# ZHSD-POWER.net
KiCad netlist of a schematic drawn in Altium Designer
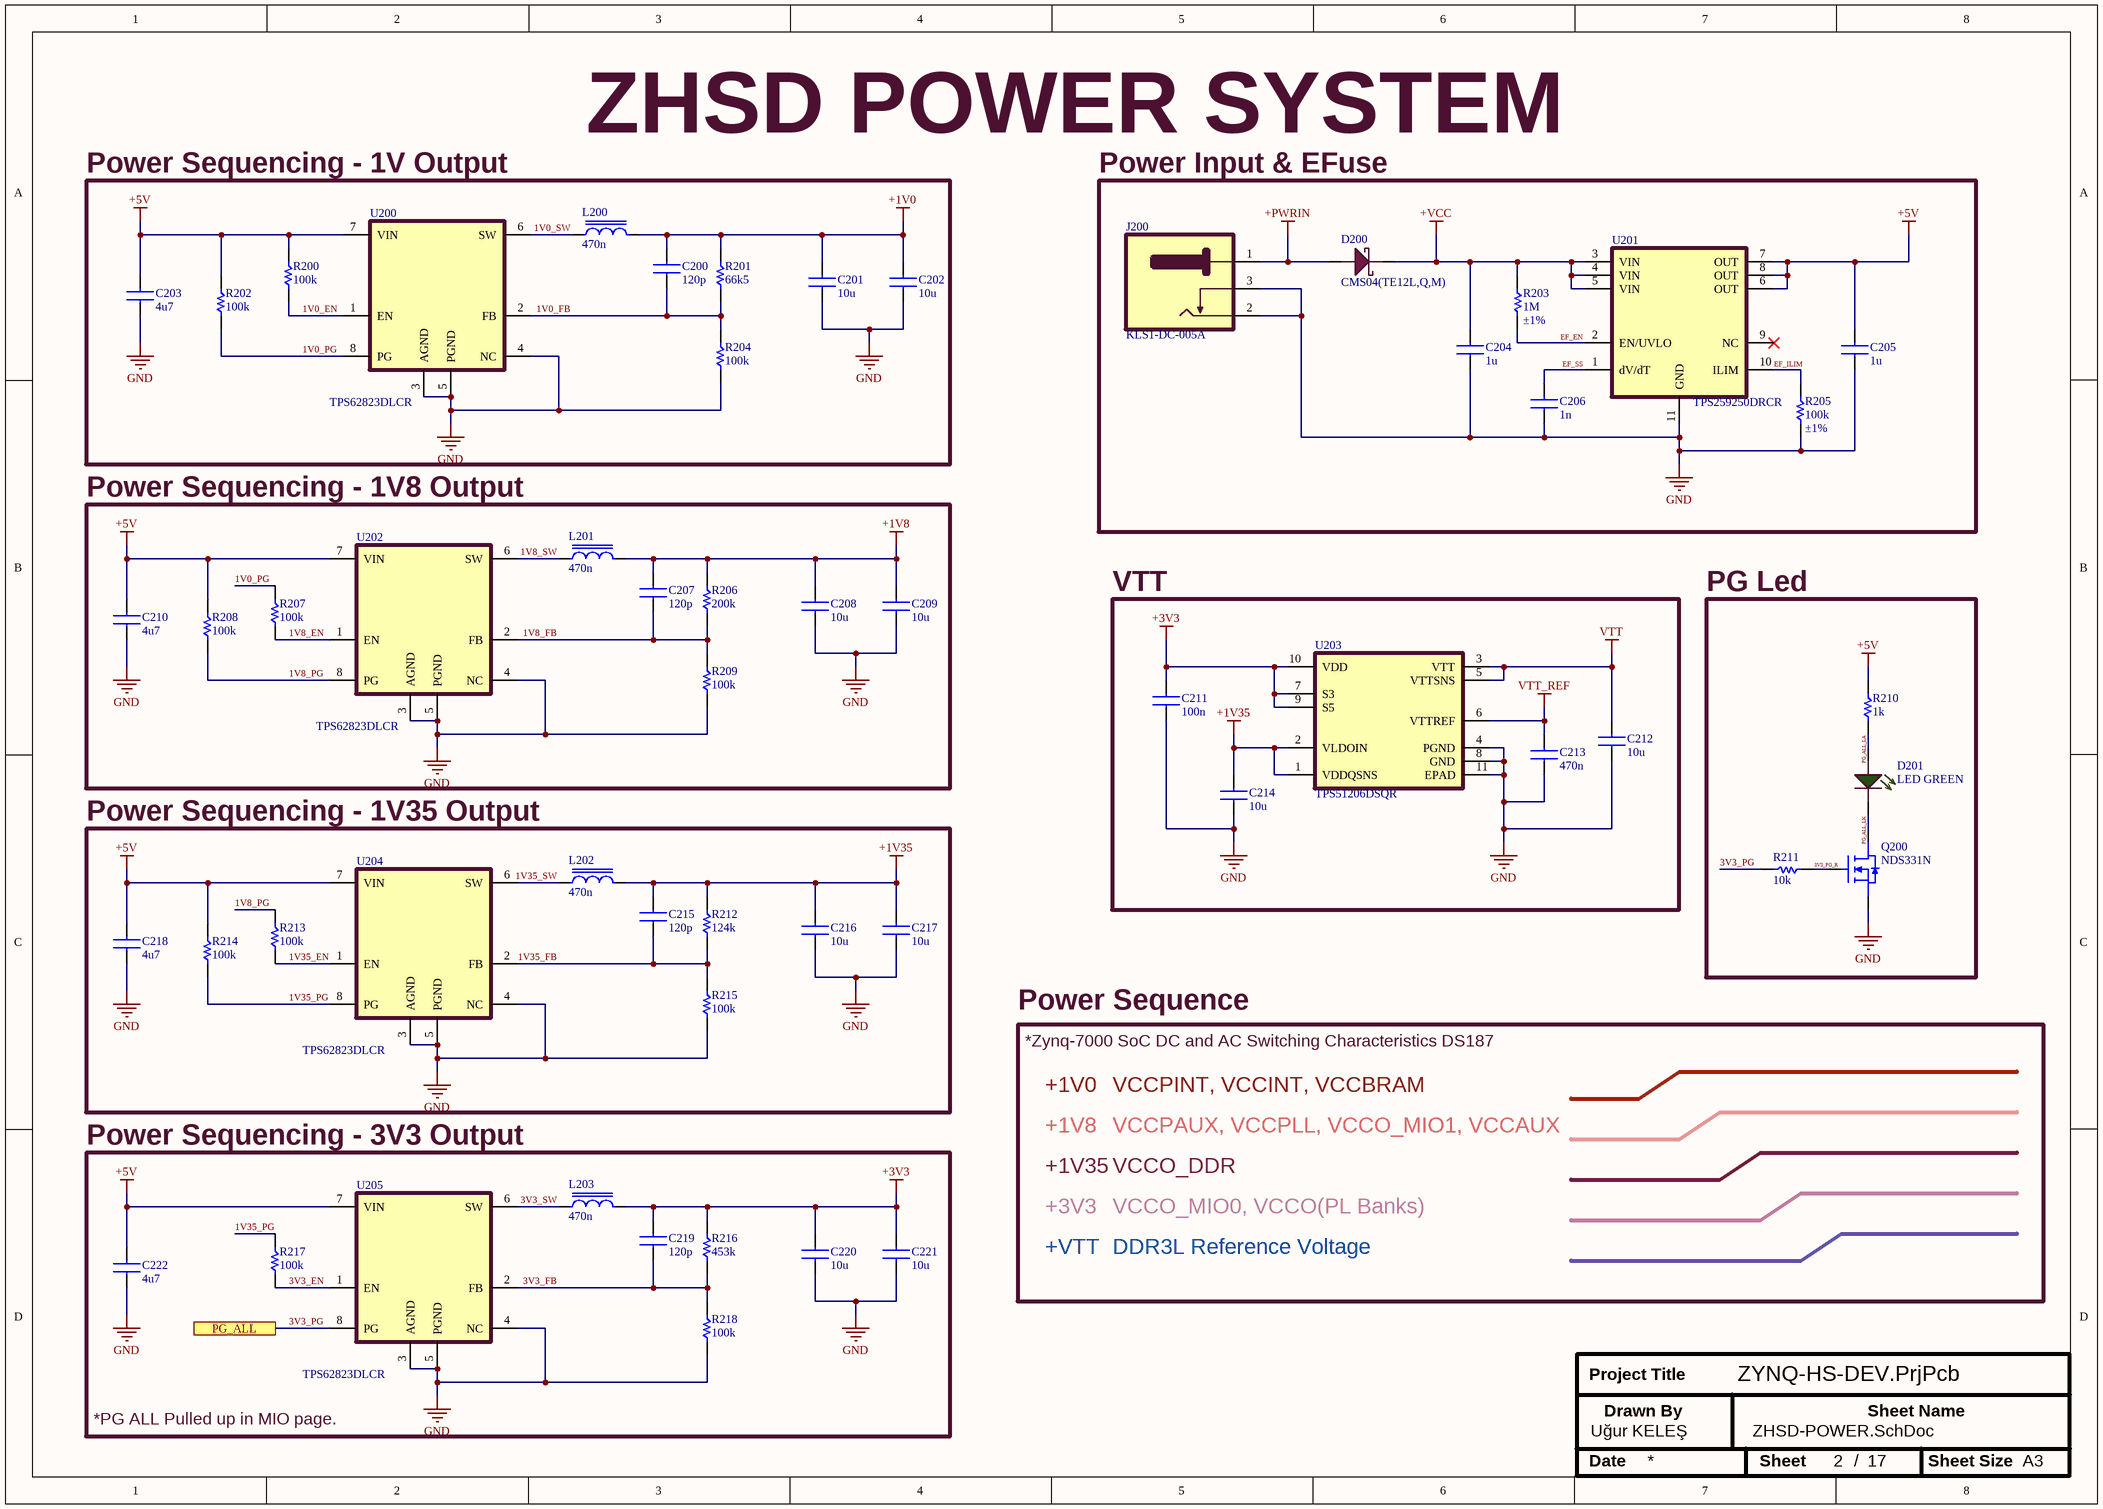
[diagram p0: ZHSD-POWER.SchDoc]

(export (version "E")
  (design (tool "Eeschema 10.0.6"))
  (components
    (comp (ref "C200")
      (value "120p")
      (footprint "0603CAPC1608X09N")
      (description "CAP CER 120PF 50V C0G/NP0 0603 (1608) ±5%")
      (fields (field (name "MANUFACTURER") "Murata Electronics") (field (name "MPN") "GRM1885C1H121JA01D"))
      (libsource (lib "UK_Library") (part "GRM1885C1H121JA01D"))
    )
    (comp (ref "C201")
      (value "10u")
      (footprint "0603CAPC1608X09N")
      (description "CAP CER 10UF 10V X7R 0603 (1608) ±20%")
      (fields (field (name "MANUFACTURER") "Murata Electronics") (field (name "MPN") "GRM188Z71A106MA73D"))
      (libsource (lib "UK_Library") (part "GRM188Z71A106MA73D"))
    )
    (comp (ref "C202")
      (value "10u")
      (footprint "0603CAPC1608X09N")
      (description "CAP CER 10UF 10V X7R 0603 (1608) ±20%")
      (fields (field (name "MANUFACTURER") "Murata Electronics") (field (name "MPN") "GRM188Z71A106MA73D"))
      (libsource (lib "UK_Library") (part "GRM188Z71A106MA73D"))
    )
    (comp (ref "C203")
      (value "4u7")
      (footprint "0805CAPC2012X14N")
      (description "CAP CER 4.7UF 10V X7R 0805 (2012) ±10%")
      (fields (field (name "MANUFACTURER") "Murata Electronics") (field (name "MPN") "GRM21BR71A475KE51L"))
      (libsource (lib "UK_Library") (part "GRM21BR71A475KE51L"))
    )
    (comp (ref "C204")
      (value "1u")
      (footprint "0603CAPC1608X09N")
      (description "CAP CER 1UF 25V X5R 0603 (1608) ±10%")
      (fields
        (field (name "MANUFACTURER") "Murata Power Solutions Inc.")
        (field (name "MPN") "GRM188R61E105KA12D")
      )
      (libsource (lib "UK_Library") (part "GRM188R61E105KA12D"))
    )
    (comp (ref "C205")
      (value "1u")
      (footprint "0603CAPC1608X09N")
      (description "CAP CER 1UF 25V X5R 0603 (1608) ±10%")
      (fields
        (field (name "MANUFACTURER") "Murata Power Solutions Inc.")
        (field (name "MPN") "GRM188R61E105KA12D")
      )
      (libsource (lib "UK_Library") (part "GRM188R61E105KA12D"))
    )
    (comp (ref "C206")
      (value "1n")
      (footprint "0603CAPC1608X09N")
      (description "CAP CER 1000PF 50V X7R 0603 (1608) ±10%")
      (fields (field (name "MANUFACTURER") "Murata Electronics") (field (name "MPN") "GCM188R71H102KA37D"))
      (libsource (lib "UK_Library") (part "GCM188R71H102KA37D"))
    )
    (comp (ref "C207")
      (value "120p")
      (footprint "0603CAPC1608X09N")
      (description "CAP CER 120PF 50V C0G/NP0 0603 (1608) ±5%")
      (fields (field (name "MANUFACTURER") "Murata Electronics") (field (name "MPN") "GRM1885C1H121JA01D"))
      (libsource (lib "UK_Library") (part "GRM1885C1H121JA01D"))
    )
    (comp (ref "C208")
      (value "10u")
      (footprint "0603CAPC1608X09N")
      (description "CAP CER 10UF 10V X7R 0603 (1608) ±20%")
      (fields (field (name "MANUFACTURER") "Murata Electronics") (field (name "MPN") "GRM188Z71A106MA73D"))
      (libsource (lib "UK_Library") (part "GRM188Z71A106MA73D"))
    )
    (comp (ref "C209")
      (value "10u")
      (footprint "0603CAPC1608X09N")
      (description "CAP CER 10UF 10V X7R 0603 (1608) ±20%")
      (fields (field (name "MANUFACTURER") "Murata Electronics") (field (name "MPN") "GRM188Z71A106MA73D"))
      (libsource (lib "UK_Library") (part "GRM188Z71A106MA73D"))
    )
    (comp (ref "C210")
      (value "4u7")
      (footprint "0805CAPC2012X14N")
      (description "CAP CER 4.7UF 10V X7R 0805 (2012) ±10%")
      (fields (field (name "MANUFACTURER") "Murata Electronics") (field (name "MPN") "GRM21BR71A475KE51L"))
      (libsource (lib "UK_Library") (part "GRM21BR71A475KE51L"))
    )
    (comp (ref "C211")
      (value "100n")
      (footprint "0402CAPC1005X06N")
      (description "CAP CER 0.1UF 16V X7R 0402 (1005) ±10%")
      (fields (field (name "MANUFACTURER") "Murata Electronics") (field (name "MPN") "GRM155R71C104KA88J"))
      (libsource (lib "UK_Library_SCH") (part "GRM155R71C104KA88J"))
    )
    (comp (ref "C212")
      (value "10u")
      (footprint "0603CAPC1608X09N")
      (description "CAP CER 10UF 10V X7R 0603 (1608) ±20%")
      (fields (field (name "MANUFACTURER") "Murata Electronics") (field (name "MPN") "GRM188Z71A106MA73D"))
      (libsource (lib "UK_Library") (part "GRM188Z71A106MA73D"))
    )
    (comp (ref "C213")
      (value "470n")
      (footprint "0402CAPC1005X06N")
      (description "CAP CER 0.47UF 6.3V X5R 0402(1005) ±10%")
      (fields (field (name "MANUFACTURER") "Murata Electronics") (field (name "MPN") "GRM155R60J474KE19D"))
      (libsource (lib "UK_Library") (part "GRM155R60J474KE19D"))
    )
    (comp (ref "C214")
      (value "10u")
      (footprint "0603CAPC1608X09N")
      (description "CAP CER 10UF 10V X7R 0603 (1608) ±20%")
      (fields (field (name "MANUFACTURER") "Murata Electronics") (field (name "MPN") "GRM188Z71A106MA73D"))
      (libsource (lib "UK_Library") (part "GRM188Z71A106MA73D"))
    )
    (comp (ref "C215")
      (value "120p")
      (footprint "0603CAPC1608X09N")
      (description "CAP CER 120PF 50V C0G/NP0 0603 (1608) ±5%")
      (fields (field (name "MANUFACTURER") "Murata Electronics") (field (name "MPN") "GRM1885C1H121JA01D"))
      (libsource (lib "UK_Library") (part "GRM1885C1H121JA01D"))
    )
    (comp (ref "C216")
      (value "10u")
      (footprint "0603CAPC1608X09N")
      (description "CAP CER 10UF 10V X7R 0603 (1608) ±20%")
      (fields (field (name "MANUFACTURER") "Murata Electronics") (field (name "MPN") "GRM188Z71A106MA73D"))
      (libsource (lib "UK_Library") (part "GRM188Z71A106MA73D"))
    )
    (comp (ref "C217")
      (value "10u")
      (footprint "0603CAPC1608X09N")
      (description "CAP CER 10UF 10V X7R 0603 (1608) ±20%")
      (fields (field (name "MANUFACTURER") "Murata Electronics") (field (name "MPN") "GRM188Z71A106MA73D"))
      (libsource (lib "UK_Library") (part "GRM188Z71A106MA73D"))
    )
    (comp (ref "C218")
      (value "4u7")
      (footprint "0805CAPC2012X14N")
      (description "CAP CER 4.7UF 10V X7R 0805 (2012) ±10%")
      (fields (field (name "MANUFACTURER") "Murata Electronics") (field (name "MPN") "GRM21BR71A475KE51L"))
      (libsource (lib "UK_Library") (part "GRM21BR71A475KE51L"))
    )
    (comp (ref "C219")
      (value "120p")
      (footprint "0603CAPC1608X09N")
      (description "CAP CER 120PF 50V C0G/NP0 0603 (1608) ±5%")
      (fields (field (name "MANUFACTURER") "Murata Electronics") (field (name "MPN") "GRM1885C1H121JA01D"))
      (libsource (lib "UK_Library") (part "GRM1885C1H121JA01D"))
    )
    (comp (ref "C220")
      (value "10u")
      (footprint "0603CAPC1608X09N")
      (description "CAP CER 10UF 10V X7R 0603 (1608) ±20%")
      (fields (field (name "MANUFACTURER") "Murata Electronics") (field (name "MPN") "GRM188Z71A106MA73D"))
      (libsource (lib "UK_Library") (part "GRM188Z71A106MA73D"))
    )
    (comp (ref "C221")
      (value "10u")
      (footprint "0603CAPC1608X09N")
      (description "CAP CER 10UF 10V X7R 0603 (1608) ±20%")
      (fields (field (name "MANUFACTURER") "Murata Electronics") (field (name "MPN") "GRM188Z71A106MA73D"))
      (libsource (lib "UK_Library") (part "GRM188Z71A106MA73D"))
    )
    (comp (ref "C222")
      (value "4u7")
      (footprint "0805CAPC2012X14N")
      (description "CAP CER 4.7UF 10V X7R 0805 (2012) ±10%")
      (fields (field (name "MANUFACTURER") "Murata Electronics") (field (name "MPN") "GRM21BR71A475KE51L"))
      (libsource (lib "UK_Library") (part "GRM21BR71A475KE51L"))
    )
    (comp (ref "D200")
      (value "CMS04(TE12L,Q,M)")
      (footprint "SOD-128")
      (description "Diode 30 V 5A Surface Mount M-FLAT (2.4x3.8)")
      (fields
        (field (name "MANUFACTURER") "Toshiba Semiconductor and Storage")
        (field (name "MPN") "CMS04(TE12L,Q")
      )
      (libsource (lib "UK_Library") (part "CMS04"))
    )
    (comp (ref "D201")
      (value "LED GREEN")
      (footprint "0603_LED_1608N")
      (description "LED GREEN CLEAR CHIP SMD")
      (fields (field (name "MANUFACTURER") "Lite-On Inc.") (field (name "MPN") "LTST-C191TGKT"))
      (libsource (lib "UK_Library") (part "LTST-C191TGKT"))
    )
    (comp (ref "J200")
      (value "KLS1-DC-005A")
      (footprint "CONN-KLS1-DC-005A")
      (description "CONNECTOR DC JACK POWER PCB TYPE 2.50MM KLS")
      (fields (field (name "MANUFACTURER") "KLS ELECTRONIC") (field (name "MPN") "L-KLS1-DC-005A-2.0"))
      (libsource (lib "UK_Library") (part "KLS1-DC-005A"))
    )
    (comp (ref "L200")
      (value "470n")
      (footprint "0806INDC2016X10N")
      (description "FIXED IND 470NH 3.6A 32 MOHM SMD 0806 (2016 Metric)")
      (fields (field (name "MANUFACTURER") "Murata Electronics") (field (name "MPN") "DFE201610E-R47M=P2"))
      (libsource (lib "UK_Library") (part "DFE201610E-R47M=P2"))
    )
    (comp (ref "L201")
      (value "470n")
      (footprint "0806INDC2016X10N")
      (description "FIXED IND 470NH 3.6A 32 MOHM SMD 0806 (2016 Metric)")
      (fields (field (name "MANUFACTURER") "Murata Electronics") (field (name "MPN") "DFE201610E-R47M=P2"))
      (libsource (lib "UK_Library") (part "DFE201610E-R47M=P2"))
    )
    (comp (ref "L202")
      (value "470n")
      (footprint "0806INDC2016X10N")
      (description "FIXED IND 470NH 3.6A 32 MOHM SMD 0806 (2016 Metric)")
      (fields (field (name "MANUFACTURER") "Murata Electronics") (field (name "MPN") "DFE201610E-R47M=P2"))
      (libsource (lib "UK_Library") (part "DFE201610E-R47M=P2"))
    )
    (comp (ref "L203")
      (value "470n")
      (footprint "0806INDC2016X10N")
      (description "FIXED IND 470NH 3.6A 32 MOHM SMD 0806 (2016 Metric)")
      (fields (field (name "MANUFACTURER") "Murata Electronics") (field (name "MPN") "DFE201610E-R47M=P2"))
      (libsource (lib "UK_Library") (part "DFE201610E-R47M=P2"))
    )
    (comp (ref "Q200")
      (value "NDS331N")
      (footprint "SOT95P251X112-3N")
      (description "N-Channel 20 V 1.3A (Ta) 500mW (Ta) Surface Mount SOT-23-3")
      (fields (field (name "MANUFACTURER") "onsemi"))
      (libsource (lib "UK_Library") (part "NDS331N"))
    )
    (comp (ref "R200")
      (value "100k")
      (footprint "0603RESC1608X05L")
      (description "RES SMD 100K OHM 1% 1/8W 0603 (1608)")
      (fields (field (name "MANUFACTURER") "Vishay Dale") (field (name "MPN") "CRCW0603100KFKEA"))
      (libsource (lib "UK_Library") (part "CRCW0603100KFKEA"))
    )
    (comp (ref "R201")
      (value "66k5")
      (footprint "0603RESC1608X05N")
      (description "RES SMD 66.5K OHM 1% 1/8W 0603 (1608)")
      (fields (field (name "MANUFACTURER") "Vishay Dale") (field (name "MPN") "CRCW060366K5FKEA"))
      (libsource (lib "UK_Library") (part "CRCW060366K5FKEA"))
    )
    (comp (ref "R202")
      (value "100k")
      (footprint "0603RESC1608X05L")
      (description "RES SMD 100K OHM 1% 1/8W 0603 (1608)")
      (fields (field (name "MANUFACTURER") "Vishay Dale") (field (name "MPN") "CRCW0603100KFKEA"))
      (libsource (lib "UK_Library") (part "CRCW0603100KFKEA"))
    )
    (comp (ref "R203")
      (value "1M")
      (footprint "0603RESC1608X05N")
      (description "RES SMD 1M OHM 1% 1/8W 0603 (1608)")
      (fields
        (field (name "MANUFACTURER") "Vishay Dale")
        (field (name "MPN") "CRCW06031M00FKEA")
        (field (name "TOLERANCE") "±1%")
      )
      (libsource (lib "UK_Library") (part "CRCW06031M00FKEA"))
    )
    (comp (ref "R204")
      (value "100k")
      (footprint "0603RESC1608X05L")
      (description "RES SMD 100K OHM 1% 1/8W 0603 (1608)")
      (fields (field (name "MANUFACTURER") "Vishay Dale") (field (name "MPN") "CRCW0603100KFKEA"))
      (libsource (lib "UK_Library") (part "CRCW0603100KFKEA"))
    )
    (comp (ref "R205")
      (value "100k")
      (footprint "0603RESC1608X05L")
      (description "RES SMD 100K OHM 1% 1/8W 0603 (1608)")
      (fields
        (field (name "MANUFACTURER") "Vishay Dale")
        (field (name "MPN") "CRCW0603100KFKEA")
        (field (name "TOLERANCE") "±1%")
      )
      (libsource (lib "UK_Library") (part "CRCW0603100KFKEA"))
    )
    (comp (ref "R206")
      (value "200k")
      (footprint "0603RESC1608X05N")
      (description "RES 200K OHM 1% 1/10W 0603 (1608)")
      (fields (field (name "MANUFACTURER") "Vishay Dale") (field (name "MPN") "CRCW0603200KFKEBC"))
      (libsource (lib "UK_Library") (part "CRCW0603200KFKEBC"))
    )
    (comp (ref "R207")
      (value "100k")
      (footprint "0603RESC1608X05L")
      (description "RES SMD 100K OHM 1% 1/8W 0603 (1608)")
      (fields (field (name "MANUFACTURER") "Vishay Dale") (field (name "MPN") "CRCW0603100KFKEA"))
      (libsource (lib "UK_Library") (part "CRCW0603100KFKEA"))
    )
    (comp (ref "R208")
      (value "100k")
      (footprint "0603RESC1608X05L")
      (description "RES SMD 100K OHM 1% 1/8W 0603 (1608)")
      (fields (field (name "MANUFACTURER") "Vishay Dale") (field (name "MPN") "CRCW0603100KFKEA"))
      (libsource (lib "UK_Library") (part "CRCW0603100KFKEA"))
    )
    (comp (ref "R209")
      (value "100k")
      (footprint "0603RESC1608X05L")
      (description "RES SMD 100K OHM 1% 1/8W 0603 (1608)")
      (fields (field (name "MANUFACTURER") "Vishay Dale") (field (name "MPN") "CRCW0603100KFKEA"))
      (libsource (lib "UK_Library") (part "CRCW0603100KFKEA"))
    )
    (comp (ref "R210")
      (value "1k")
      (footprint "0402RESC1005X04N")
      (description "RES 1K OHM 5% 1/16W 0402 (1005)")
      (fields (field (name "MANUFACTURER") "YAGEO") (field (name "MPN") "RC0402JR-071KL"))
      (libsource (lib "UK_Library") (part "RC0402JR-071KL"))
    )
    (comp (ref "R211")
      (value "10k")
      (footprint "0603RESC1608X05N")
      (description "RES 10K OHM 1% 1/10W 0603(1608)")
      (fields (field (name "MANUFACTURER") "YAGEO") (field (name "MPN") "RC0603FR-0710KL"))
      (libsource (lib "UK_Library") (part "RC0603FR-0710KL"))
    )
    (comp (ref "R212")
      (value "124k")
      (footprint "0603RESC1608X05N")
      (description "RES SMD 124K OHM 1% 1/8W 0603 (1608)")
      (fields (field (name "MANUFACTURER") "Vishay Dale") (field (name "MPN") "CRCW0603124KFKEA"))
      (libsource (lib "UK_Library") (part "CRCW0603124KFKEA"))
    )
    (comp (ref "R213")
      (value "100k")
      (footprint "0603RESC1608X05L")
      (description "RES SMD 100K OHM 1% 1/8W 0603 (1608)")
      (fields (field (name "MANUFACTURER") "Vishay Dale") (field (name "MPN") "CRCW0603100KFKEA"))
      (libsource (lib "UK_Library") (part "CRCW0603100KFKEA"))
    )
    (comp (ref "R214")
      (value "100k")
      (footprint "0603RESC1608X05L")
      (description "RES SMD 100K OHM 1% 1/8W 0603 (1608)")
      (fields (field (name "MANUFACTURER") "Vishay Dale") (field (name "MPN") "CRCW0603100KFKEA"))
      (libsource (lib "UK_Library") (part "CRCW0603100KFKEA"))
    )
    (comp (ref "R215")
      (value "100k")
      (footprint "0603RESC1608X05L")
      (description "RES SMD 100K OHM 1% 1/8W 0603 (1608)")
      (fields (field (name "MANUFACTURER") "Vishay Dale") (field (name "MPN") "CRCW0603100KFKEA"))
      (libsource (lib "UK_Library") (part "CRCW0603100KFKEA"))
    )
    (comp (ref "R216")
      (value "453k")
      (footprint "0603RESC1608X05N")
      (description "RES 453K OHM 1% 1/10W 0603(1608)")
      (fields (field (name "MANUFACTURER") "Vishay Dale") (field (name "MPN") "CRCW0603453KFKEAC"))
      (libsource (lib "UK_Library") (part "CRCW0603453KFKEAC"))
    )
    (comp (ref "R217")
      (value "100k")
      (footprint "0603RESC1608X05L")
      (description "RES SMD 100K OHM 1% 1/8W 0603 (1608)")
      (fields (field (name "MANUFACTURER") "Vishay Dale") (field (name "MPN") "CRCW0603100KFKEA"))
      (libsource (lib "UK_Library") (part "CRCW0603100KFKEA"))
    )
    (comp (ref "R218")
      (value "100k")
      (footprint "0603RESC1608X05L")
      (description "RES SMD 100K OHM 1% 1/8W 0603 (1608)")
      (fields (field (name "MANUFACTURER") "Vishay Dale") (field (name "MPN") "CRCW0603100KFKEA"))
      (libsource (lib "UK_Library") (part "CRCW0603100KFKEA"))
    )
    (comp (ref "U200")
      (value "TPS62823DLCR")
      (footprint "VSON50P150X100-8N")
      (description "2.4-V to 5.5-V input, 3-A step-down converter with 1% accuracy in 1.5-mm x 2-mm VSON-HR package")
      (fields (field (name "MANUFACTURER") "Texas Instruments"))
      (libsource (lib "UK_Library") (part "TPS62823DLCR"))
    )
    (comp (ref "U201")
      (value "TPS259250DRCR")
      (footprint "VSON50P300X100_HS-11N")
      (description "Electronic Fuse Regulator 5A 10-VSON (3x3)")
      (fields (field (name "MANUFACTURER") "Texas Instruments"))
      (libsource (lib "UK_Library") (part "TPS259250DRCR"))
    )
    (comp (ref "U202")
      (value "TPS62823DLCR")
      (footprint "VSON50P150X100-8N")
      (description "2.4-V to 5.5-V input, 3-A step-down converter with 1% accuracy in 1.5-mm x 2-mm VSON-HR package")
      (fields (field (name "MANUFACTURER") "Texas Instruments"))
      (libsource (lib "UK_Library") (part "TPS62823DLCR"))
    )
    (comp (ref "U203")
      (value "TPS51206DSQR")
      (footprint "WSON2X2-10/SON40P200X80_HS-11N")
      (description "Converter, DDR Voltage Regulator IC 1 Output 10-WSON (2x2)")
      (fields (field (name "MANUFACTURER") "Texas Instruments"))
      (libsource (lib "UK_Library") (part "TPS51206"))
    )
    (comp (ref "U204")
      (value "TPS62823DLCR")
      (footprint "VSON50P150X100-8N")
      (description "2.4-V to 5.5-V input, 3-A step-down converter with 1% accuracy in 1.5-mm x 2-mm VSON-HR package")
      (fields (field (name "MANUFACTURER") "Texas Instruments"))
      (libsource (lib "UK_Library") (part "TPS62823DLCR"))
    )
    (comp (ref "U205")
      (value "TPS62823DLCR")
      (footprint "VSON50P150X100-8N")
      (description "2.4-V to 5.5-V input, 3-A step-down converter with 1% accuracy in 1.5-mm x 2-mm VSON-HR package")
      (fields (field (name "MANUFACTURER") "Texas Instruments"))
      (libsource (lib "UK_Library") (part "TPS62823DLCR"))
    )
  )
  (nets
    (net (code "1") (name "+1V0") (class "Default")
      (node (ref "C200") (pin "2") (pinfunction "2_2") (pintype "passive"))
      (node (ref "C201") (pin "2") (pinfunction "2_2") (pintype "passive"))
      (node (ref "C202") (pin "2") (pinfunction "2_2") (pintype "passive"))
      (node (ref "L200") (pin "2") (pinfunction "2_2") (pintype "passive"))
      (node (ref "R201") (pin "2") (pinfunction "2_2") (pintype "passive"))
    )
    (net (code "2") (name "+1V8") (class "Default")
      (node (ref "C207") (pin "2") (pinfunction "2_2") (pintype "passive"))
      (node (ref "C208") (pin "2") (pinfunction "2_2") (pintype "passive"))
      (node (ref "C209") (pin "2") (pinfunction "2_2") (pintype "passive"))
      (node (ref "L201") (pin "2") (pinfunction "2_2") (pintype "passive"))
      (node (ref "R206") (pin "2") (pinfunction "2_2") (pintype "passive"))
    )
    (net (code "3") (name "+1V35") (class "Default")
      (node (ref "C214") (pin "2") (pinfunction "2_2") (pintype "passive"))
      (node (ref "C215") (pin "2") (pinfunction "2_2") (pintype "passive"))
      (node (ref "C216") (pin "2") (pinfunction "2_2") (pintype "passive"))
      (node (ref "C217") (pin "2") (pinfunction "2_2") (pintype "passive"))
      (node (ref "L202") (pin "2") (pinfunction "2_2") (pintype "passive"))
      (node (ref "R212") (pin "2") (pinfunction "2_2") (pintype "passive"))
      (node (ref "U203") (pin "1") (pinfunction "VDDQSNS_1") (pintype "power_in"))
      (node (ref "U203") (pin "2") (pinfunction "VLDOIN_2") (pintype "power_in"))
    )
    (net (code "4") (name "+3V3") (class "Default")
      (node (ref "C211") (pin "2") (pinfunction "2_2") (pintype "passive"))
      (node (ref "C219") (pin "2") (pinfunction "2_2") (pintype "passive"))
      (node (ref "C220") (pin "2") (pinfunction "2_2") (pintype "passive"))
      (node (ref "C221") (pin "2") (pinfunction "2_2") (pintype "passive"))
      (node (ref "L203") (pin "2") (pinfunction "2_2") (pintype "passive"))
      (node (ref "R216") (pin "2") (pinfunction "2_2") (pintype "passive"))
      (node (ref "U203") (pin "10") (pinfunction "VDD_10") (pintype "power_in"))
      (node (ref "U203") (pin "7") (pinfunction "S3_7") (pintype "power_in"))
      (node (ref "U203") (pin "9") (pinfunction "S5_9") (pintype "power_in"))
    )
    (net (code "5") (name "+5V") (class "Default")
      (node (ref "C203") (pin "2") (pinfunction "2_2") (pintype "passive"))
      (node (ref "C205") (pin "2") (pinfunction "2_2") (pintype "passive"))
      (node (ref "C210") (pin "2") (pinfunction "2_2") (pintype "passive"))
      (node (ref "C218") (pin "2") (pinfunction "2_2") (pintype "passive"))
      (node (ref "C222") (pin "2") (pinfunction "2_2") (pintype "passive"))
      (node (ref "R200") (pin "2") (pinfunction "2_2") (pintype "passive"))
      (node (ref "R202") (pin "2") (pinfunction "2_2") (pintype "passive"))
      (node (ref "R208") (pin "2") (pinfunction "2_2") (pintype "passive"))
      (node (ref "R210") (pin "2") (pinfunction "2_2") (pintype "passive"))
      (node (ref "R214") (pin "2") (pinfunction "2_2") (pintype "passive"))
      (node (ref "U200") (pin "7") (pinfunction "VIN_7") (pintype "power_in"))
      (node (ref "U201") (pin "6") (pinfunction "OUT_6") (pintype "power_in"))
      (node (ref "U201") (pin "7") (pinfunction "OUT_7") (pintype "power_in"))
      (node (ref "U201") (pin "8") (pinfunction "OUT_8") (pintype "power_in"))
      (node (ref "U202") (pin "7") (pinfunction "VIN_7") (pintype "power_in"))
      (node (ref "U204") (pin "7") (pinfunction "VIN_7") (pintype "power_in"))
      (node (ref "U205") (pin "7") (pinfunction "VIN_7") (pintype "power_in"))
    )
    (net (code "6") (name "+PWRIN") (class "Default")
      (node (ref "D200") (pin "A") (pinfunction "2_A") (pintype "passive"))
      (node (ref "J200") (pin "1") (pinfunction "VCC_1") (pintype "passive"))
    )
    (net (code "7") (name "+VCC") (class "Default")
      (node (ref "C204") (pin "2") (pinfunction "2_2") (pintype "passive"))
      (node (ref "D200") (pin "C") (pinfunction "1_C") (pintype "passive"))
      (node (ref "R203") (pin "1") (pinfunction "1_1") (pintype "passive"))
      (node (ref "U201") (pin "3") (pinfunction "VIN_3") (pintype "power_in"))
      (node (ref "U201") (pin "4") (pinfunction "VIN_4") (pintype "power_in"))
      (node (ref "U201") (pin "5") (pinfunction "VIN_5") (pintype "power_in"))
    )
    (net (code "8") (name "/1V0_EN") (class "Default")
      (node (ref "R200") (pin "1") (pinfunction "1_1") (pintype "passive"))
      (node (ref "U200") (pin "1") (pinfunction "EN_1") (pintype "passive"))
    )
    (net (code "9") (name "/1V0_FB") (class "Default")
      (node (ref "C200") (pin "1") (pinfunction "1_1") (pintype "passive"))
      (node (ref "R201") (pin "1") (pinfunction "1_1") (pintype "passive"))
      (node (ref "R204") (pin "2") (pinfunction "2_2") (pintype "passive"))
      (node (ref "U200") (pin "2") (pinfunction "FB_2") (pintype "passive"))
    )
    (net (code "10") (name "/1V0_PG") (class "Default")
      (node (ref "R202") (pin "1") (pinfunction "1_1") (pintype "passive"))
      (node (ref "R207") (pin "2") (pinfunction "2_2") (pintype "passive"))
      (node (ref "U200") (pin "8") (pinfunction "PG_8") (pintype "passive"))
    )
    (net (code "11") (name "/1V0_SW") (class "Default")
      (node (ref "L200") (pin "1") (pinfunction "1_1") (pintype "passive"))
      (node (ref "U200") (pin "6") (pinfunction "SW_6") (pintype "power_in"))
    )
    (net (code "12") (name "/1V8_EN") (class "Default")
      (node (ref "R207") (pin "1") (pinfunction "1_1") (pintype "passive"))
      (node (ref "U202") (pin "1") (pinfunction "EN_1") (pintype "passive"))
    )
    (net (code "13") (name "/1V8_FB") (class "Default")
      (node (ref "C207") (pin "1") (pinfunction "1_1") (pintype "passive"))
      (node (ref "R206") (pin "1") (pinfunction "1_1") (pintype "passive"))
      (node (ref "R209") (pin "2") (pinfunction "2_2") (pintype "passive"))
      (node (ref "U202") (pin "2") (pinfunction "FB_2") (pintype "passive"))
    )
    (net (code "14") (name "/1V8_PG") (class "Default")
      (node (ref "R208") (pin "1") (pinfunction "1_1") (pintype "passive"))
      (node (ref "R213") (pin "2") (pinfunction "2_2") (pintype "passive"))
      (node (ref "U202") (pin "8") (pinfunction "PG_8") (pintype "passive"))
    )
    (net (code "15") (name "/1V8_SW") (class "Default")
      (node (ref "L201") (pin "1") (pinfunction "1_1") (pintype "passive"))
      (node (ref "U202") (pin "6") (pinfunction "SW_6") (pintype "power_in"))
    )
    (net (code "16") (name "/1V35_EN") (class "Default")
      (node (ref "R213") (pin "1") (pinfunction "1_1") (pintype "passive"))
      (node (ref "U204") (pin "1") (pinfunction "EN_1") (pintype "passive"))
    )
    (net (code "17") (name "/1V35_FB") (class "Default")
      (node (ref "C215") (pin "1") (pinfunction "1_1") (pintype "passive"))
      (node (ref "R212") (pin "1") (pinfunction "1_1") (pintype "passive"))
      (node (ref "R215") (pin "2") (pinfunction "2_2") (pintype "passive"))
      (node (ref "U204") (pin "2") (pinfunction "FB_2") (pintype "passive"))
    )
    (net (code "18") (name "/1V35_PG") (class "Default")
      (node (ref "R214") (pin "1") (pinfunction "1_1") (pintype "passive"))
      (node (ref "R217") (pin "2") (pinfunction "2_2") (pintype "passive"))
      (node (ref "U204") (pin "8") (pinfunction "PG_8") (pintype "passive"))
    )
    (net (code "19") (name "/1V35_SW") (class "Default")
      (node (ref "L202") (pin "1") (pinfunction "1_1") (pintype "passive"))
      (node (ref "U204") (pin "6") (pinfunction "SW_6") (pintype "power_in"))
    )
    (net (code "20") (name "/3V3_EN") (class "Default")
      (node (ref "R217") (pin "1") (pinfunction "1_1") (pintype "passive"))
      (node (ref "U205") (pin "1") (pinfunction "EN_1") (pintype "passive"))
    )
    (net (code "21") (name "/3V3_FB") (class "Default")
      (node (ref "C219") (pin "1") (pinfunction "1_1") (pintype "passive"))
      (node (ref "R216") (pin "1") (pinfunction "1_1") (pintype "passive"))
      (node (ref "R218") (pin "2") (pinfunction "2_2") (pintype "passive"))
      (node (ref "U205") (pin "2") (pinfunction "FB_2") (pintype "passive"))
    )
    (net (code "22") (name "/3V3_PG") (class "Default")
      (node (ref "R211") (pin "2") (pinfunction "2_2") (pintype "passive"))
      (node (ref "U205") (pin "8") (pinfunction "PG_8") (pintype "passive"))
    )
    (net (code "23") (name "/3V3_PG_R") (class "Default")
      (node (ref "Q200") (pin "1") (pinfunction "G_1") (pintype "passive"))
      (node (ref "R211") (pin "1") (pinfunction "1_1") (pintype "passive"))
    )
    (net (code "24") (name "/3V3_SW") (class "Default")
      (node (ref "L203") (pin "1") (pinfunction "1_1") (pintype "passive"))
      (node (ref "U205") (pin "6") (pinfunction "SW_6") (pintype "power_in"))
    )
    (net (code "25") (name "/EF_EN") (class "Default")
      (node (ref "R203") (pin "2") (pinfunction "2_2") (pintype "passive"))
      (node (ref "U201") (pin "2") (pinfunction "EN/UVLO_2") (pintype "passive"))
    )
    (net (code "26") (name "/EF_ILIM") (class "Default")
      (node (ref "R205") (pin "2") (pinfunction "2_2") (pintype "passive"))
      (node (ref "U201") (pin "10") (pinfunction "ILIM_10") (pintype "passive"))
    )
    (net (code "27") (name "/EF_SS") (class "Default")
      (node (ref "C206") (pin "2") (pinfunction "2_2") (pintype "passive"))
      (node (ref "U201") (pin "1") (pinfunction "dV/dT_1") (pintype "passive"))
    )
    (net (code "28") (name "/PG_ALL_LA") (class "Default")
      (node (ref "D201") (pin "1") (pinfunction "A_1") (pintype "passive"))
      (node (ref "R210") (pin "1") (pinfunction "1_1") (pintype "passive"))
    )
    (net (code "29") (name "/PG_ALL_LK") (class "Default")
      (node (ref "D201") (pin "2") (pinfunction "C_2") (pintype "passive"))
      (node (ref "Q200") (pin "3") (pinfunction "D_3") (pintype "passive"))
    )
    (net (code "30") (name "GND") (class "Default")
      (node (ref "C201") (pin "1") (pinfunction "1_1") (pintype "passive"))
      (node (ref "C202") (pin "1") (pinfunction "1_1") (pintype "passive"))
      (node (ref "C203") (pin "1") (pinfunction "1_1") (pintype "passive"))
      (node (ref "C204") (pin "1") (pinfunction "1_1") (pintype "passive"))
      (node (ref "C205") (pin "1") (pinfunction "1_1") (pintype "passive"))
      (node (ref "C206") (pin "1") (pinfunction "1_1") (pintype "passive"))
      (node (ref "C208") (pin "1") (pinfunction "1_1") (pintype "passive"))
      (node (ref "C209") (pin "1") (pinfunction "1_1") (pintype "passive"))
      (node (ref "C210") (pin "1") (pinfunction "1_1") (pintype "passive"))
      (node (ref "C211") (pin "1") (pinfunction "1_1") (pintype "passive"))
      (node (ref "C212") (pin "1") (pinfunction "1_1") (pintype "passive"))
      (node (ref "C213") (pin "1") (pinfunction "1_1") (pintype "passive"))
      (node (ref "C214") (pin "1") (pinfunction "1_1") (pintype "passive"))
      (node (ref "C216") (pin "1") (pinfunction "1_1") (pintype "passive"))
      (node (ref "C217") (pin "1") (pinfunction "1_1") (pintype "passive"))
      (node (ref "C218") (pin "1") (pinfunction "1_1") (pintype "passive"))
      (node (ref "C220") (pin "1") (pinfunction "1_1") (pintype "passive"))
      (node (ref "C221") (pin "1") (pinfunction "1_1") (pintype "passive"))
      (node (ref "C222") (pin "1") (pinfunction "1_1") (pintype "passive"))
      (node (ref "J200") (pin "2") (pinfunction "GND_2") (pintype "passive"))
      (node (ref "J200") (pin "3") (pinfunction "SH_3") (pintype "passive"))
      (node (ref "Q200") (pin "2") (pinfunction "S_2") (pintype "passive"))
      (node (ref "R204") (pin "1") (pinfunction "1_1") (pintype "passive"))
      (node (ref "R205") (pin "1") (pinfunction "1_1") (pintype "passive"))
      (node (ref "R209") (pin "1") (pinfunction "1_1") (pintype "passive"))
      (node (ref "R215") (pin "1") (pinfunction "1_1") (pintype "passive"))
      (node (ref "R218") (pin "1") (pinfunction "1_1") (pintype "passive"))
      (node (ref "U200") (pin "3") (pinfunction "AGND_3") (pintype "power_in"))
      (node (ref "U200") (pin "4") (pinfunction "NC_4") (pintype "power_in"))
      (node (ref "U200") (pin "5") (pinfunction "PGND_5") (pintype "power_in"))
      (node (ref "U201") (pin "11") (pinfunction "GND_11") (pintype "power_in"))
      (node (ref "U202") (pin "3") (pinfunction "AGND_3") (pintype "power_in"))
      (node (ref "U202") (pin "4") (pinfunction "NC_4") (pintype "power_in"))
      (node (ref "U202") (pin "5") (pinfunction "PGND_5") (pintype "power_in"))
      (node (ref "U203") (pin "11") (pinfunction "EPAD_11") (pintype "power_in"))
      (node (ref "U203") (pin "4") (pinfunction "PGND_4") (pintype "power_in"))
      (node (ref "U203") (pin "8") (pinfunction "GND_8") (pintype "power_in"))
      (node (ref "U204") (pin "3") (pinfunction "AGND_3") (pintype "power_in"))
      (node (ref "U204") (pin "4") (pinfunction "NC_4") (pintype "power_in"))
      (node (ref "U204") (pin "5") (pinfunction "PGND_5") (pintype "power_in"))
      (node (ref "U205") (pin "3") (pinfunction "AGND_3") (pintype "power_in"))
      (node (ref "U205") (pin "4") (pinfunction "NC_4") (pintype "power_in"))
      (node (ref "U205") (pin "5") (pinfunction "PGND_5") (pintype "power_in"))
    )
    (net (code "31") (name "VTT") (class "Default")
      (node (ref "C212") (pin "2") (pinfunction "2_2") (pintype "passive"))
      (node (ref "U203") (pin "3") (pinfunction "VTT_3") (pintype "power_in"))
      (node (ref "U203") (pin "5") (pinfunction "VTTSNS_5") (pintype "power_in"))
    )
    (net (code "32") (name "VTT_REF") (class "Default")
      (node (ref "C213") (pin "2") (pinfunction "2_2") (pintype "passive"))
      (node (ref "U203") (pin "6") (pinfunction "VTTREF_6") (pintype "power_in"))
    )
    (net (code "33") (name "unconnected-(U201-NC-Pad9)") (class "Default")
      (node (ref "U201") (pin "9") (pinfunction "NC_9") (pintype "passive+no_connect"))
    )
  )
)
